# Comparator_Breakout_MCP6541.net
KiCad netlist of a schematic drawn in EAGLE
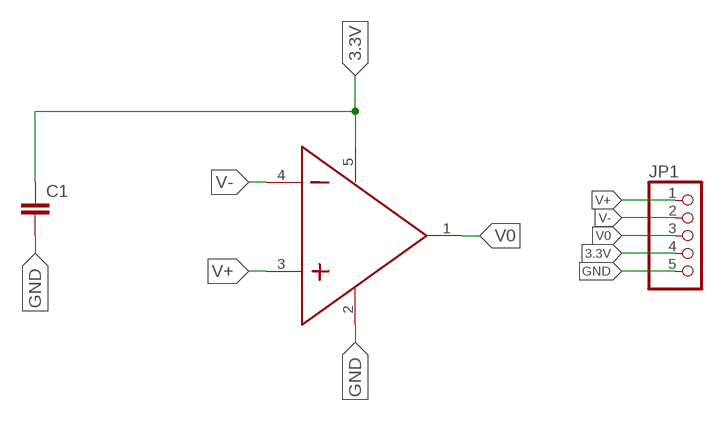
[diagram p0: schematic, sheet 1]

(export (version "E")
  (design (tool "Eeschema 10.0.6"))
  (components
    (comp (ref "C1")
      (value "C-EUC0805")
      (footprint "eagle-import:C0805")
      (libsource (lib "eagle-import") (part "C-EUC0805"))
    )
    (comp (ref "JP1")
      (value "PINHD-1X5")
      (footprint "eagle-import:1X05")
      (libsource (lib "eagle-import") (part "PINHD-1X5"))
    )
    (comp (ref "U$1")
      (value "MCP6541")
      (footprint "eagle-import:SOT23-5")
      (libsource (lib "eagle-import") (part "MCP6541"))
    )
  )
  (nets
    (net (code "1") (name "3.3V") (class "Default")
      (node (ref "C1") (pin "1") (pinfunction "1_1") (pintype "passive"))
      (node (ref "JP1") (pin "4") (pinfunction "4_4") (pintype "passive"))
      (node (ref "U$1") (pin "5") (pinfunction "VDD_5") (pintype "bidirectional"))
    )
    (net (code "2") (name "GND") (class "Default")
      (node (ref "C1") (pin "2") (pinfunction "2_2") (pintype "passive"))
      (node (ref "JP1") (pin "5") (pinfunction "5_5") (pintype "passive"))
      (node (ref "U$1") (pin "2") (pinfunction "VSS_2") (pintype "bidirectional"))
    )
    (net (code "3") (name "V+") (class "Default")
      (node (ref "JP1") (pin "1") (pinfunction "1_1") (pintype "passive"))
      (node (ref "U$1") (pin "3") (pinfunction "IN+_3") (pintype "bidirectional"))
    )
    (net (code "4") (name "V-") (class "Default")
      (node (ref "JP1") (pin "2") (pinfunction "2_2") (pintype "passive"))
      (node (ref "U$1") (pin "4") (pinfunction "IN-_4") (pintype "bidirectional"))
    )
    (net (code "5") (name "V0") (class "Default")
      (node (ref "JP1") (pin "3") (pinfunction "3_3") (pintype "passive"))
      (node (ref "U$1") (pin "1") (pinfunction "OUT_1") (pintype "bidirectional"))
    )
  )
)
